# 1_-POWER.net
KiCad netlist of a schematic drawn in Altium Designer
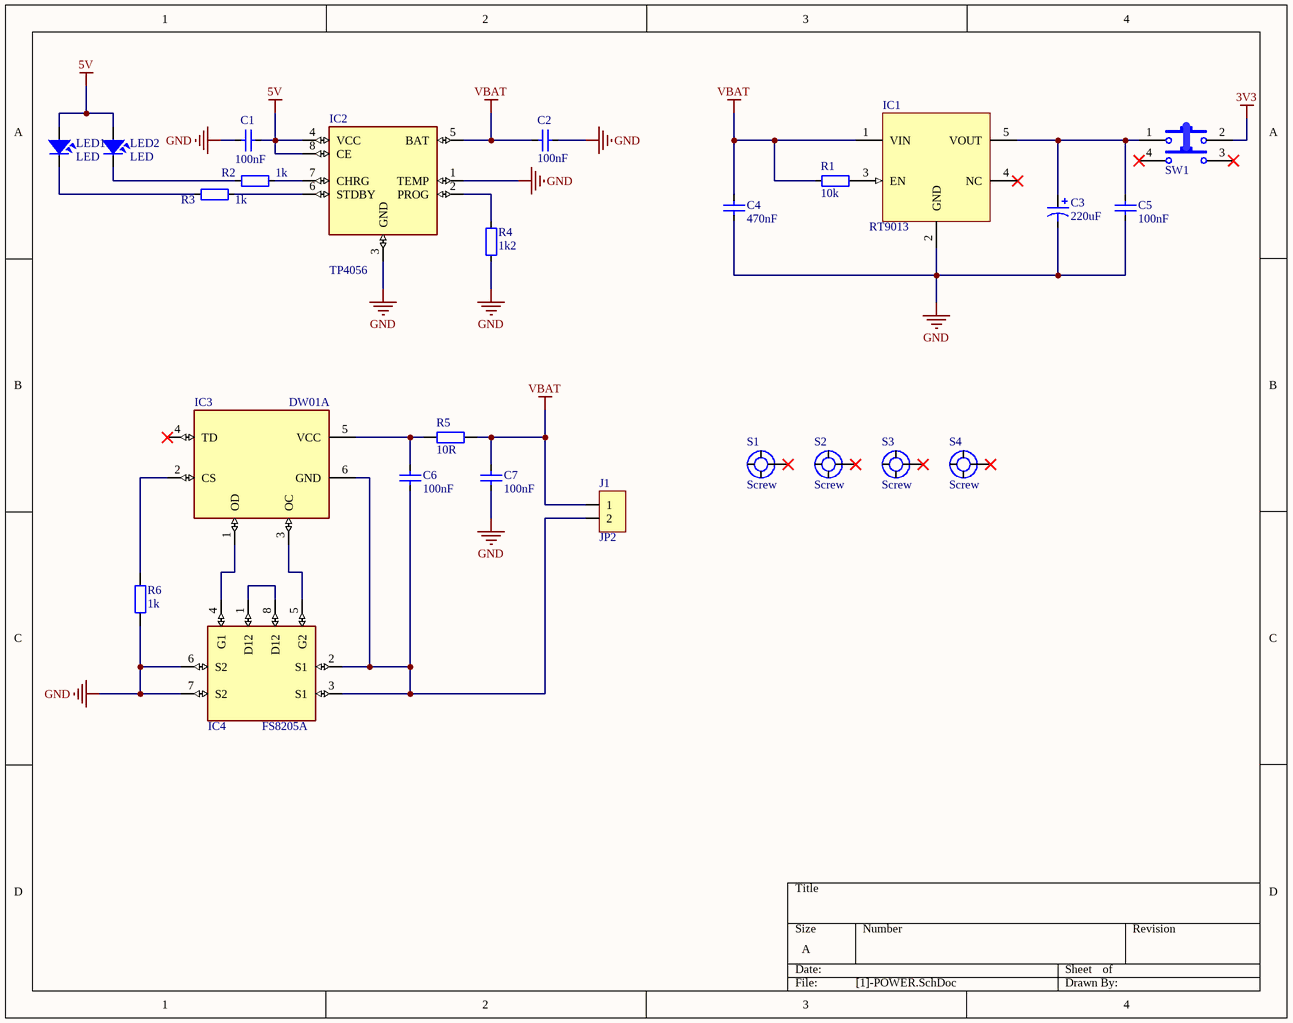
[diagram p0: [1]-POWER.SchDoc]

(export (version "E")
  (design (tool "Eeschema 10.0.6"))
  (components
    (comp (ref "C1")
      (value "100nF")
      (footprint "CAP_0805")
      (description "Capacitor")
      (fields (field (name "PUBLISHER") "Altium Limited"))
      (libsource (lib "My Library") (part "CapSMD"))
    )
    (comp (ref "C2")
      (value "100nF")
      (footprint "CAP_0805")
      (description "Capacitor")
      (fields (field (name "PUBLISHER") "Altium Limited"))
      (libsource (lib "My Library") (part "CapSMD"))
    )
    (comp (ref "C3")
      (value "220uF")
      (footprint "CAP_TANTALUM_3216")
      (description "Polarized Capacitor (Axial)")
      (fields (field (name "PUBLISHER") "Altium Limited"))
      (libsource (lib "My Library") (part "Cap Pol"))
    )
    (comp (ref "C4")
      (value "470nF")
      (footprint "CAP_0805")
      (description "Capacitor")
      (fields (field (name "PUBLISHER") "Altium Limited"))
      (libsource (lib "My Library") (part "CapSMD"))
    )
    (comp (ref "C5")
      (value "100nF")
      (footprint "CAP_0805")
      (description "Capacitor")
      (fields (field (name "PUBLISHER") "Altium Limited"))
      (libsource (lib "My Library") (part "CapSMD"))
    )
    (comp (ref "C6")
      (value "100nF")
      (footprint "CAP_0805")
      (description "Capacitor")
      (fields (field (name "PUBLISHER") "Altium Limited"))
      (libsource (lib "My Library") (part "CapSMD"))
    )
    (comp (ref "C7")
      (value "100nF")
      (footprint "CAP_0805")
      (description "Capacitor")
      (fields (field (name "PUBLISHER") "Altium Limited"))
      (libsource (lib "My Library") (part "CapSMD"))
    )
    (comp (ref "IC1")
      (value "RT9013")
      (footprint "SOT23-5")
      (description "RT9013-33GB IC REG LINEAR 3.3V 500mA SOT23-5")
      (libsource (lib "My Library") (part "RT9013"))
    )
    (comp (ref "IC2")
      (value "TP4056")
      (footprint "SOP127P600X175-9N")
      (description "Complete single cell Li-Ion battery with a constant current / constant voltage linear charger")
      (libsource (lib "My Library") (part "TP4056"))
    )
    (comp (ref "IC3")
      (value "DW01A")
      (footprint "SOT23-6")
      (description "One Cell Lithium-ion/Polymer Battery Protection IC")
      (libsource (lib "My Library") (part "DW01A"))
    )
    (comp (ref "IC4") (value "FS8205A") (footprint "FS8205A") (libsource (lib "My Library") (part "FS8205A")))
    (comp (ref "J1")
      (value "JP2")
      (footprint "CON2")
      (description "WR-PHD 2.54 mm Angled Socket Header")
      (fields
        (field (name "MANUFACTURER") "Würth Elektronik eiSos GmbH")
        (field (name "PARTNO") "613002143121")
        (field (name "CREATED BY") "Karrer Zheng")
      )
      (libsource (lib "My Library") (part "JP2"))
    )
    (comp (ref "LED1")
      (value "LED")
      (footprint "LED-0805-Red")
      (description "LED Single colour Green and Red")
      (libsource (lib "My Library") (part "LED"))
    )
    (comp (ref "LED2")
      (value "LED")
      (footprint "LED-0805-Green")
      (description "LED Single colour Green and Red")
      (libsource (lib "My Library") (part "LED"))
    )
    (comp (ref "R1")
      (value "10k")
      (footprint "RES-SMD-0805")
      (description "Resistor")
      (fields
        (field (name "MANUFACTURER") "Generic Components")
        (field (name "PUBLISHER") "Altium Hobart Technology Centre")
      )
      (libsource (lib "My Library") (part "Resistor - SMD"))
    )
    (comp (ref "R2")
      (value "1k")
      (footprint "RES-SMD-0805")
      (description "Resistor")
      (fields
        (field (name "MANUFACTURER") "Generic Components")
        (field (name "PUBLISHER") "Altium Hobart Technology Centre")
      )
      (libsource (lib "My Library") (part "Resistor - SMD"))
    )
    (comp (ref "R3")
      (value "1k")
      (footprint "RES-SMD-0805")
      (description "Resistor")
      (fields
        (field (name "MANUFACTURER") "Generic Components")
        (field (name "PUBLISHER") "Altium Hobart Technology Centre")
      )
      (libsource (lib "My Library") (part "Resistor - SMD"))
    )
    (comp (ref "R4")
      (value "1k2")
      (footprint "RES-SMD-0805")
      (description "Resistor")
      (fields
        (field (name "MANUFACTURER") "Generic Components")
        (field (name "PUBLISHER") "Altium Hobart Technology Centre")
      )
      (libsource (lib "My Library") (part "Resistor - SMD"))
    )
    (comp (ref "R5")
      (value "10R")
      (footprint "RES-SMD-0805")
      (description "Resistor SMD")
      (fields
        (field (name "MANUFACTURER") "Generic Components")
        (field (name "PUBLISHER") "Altium Hobart Technology Centre")
      )
      (libsource (lib "") (part "Resistor - SMD_1"))
    )
    (comp (ref "R6")
      (value "1k")
      (footprint "RES-SMD-0805")
      (description "Resistor SMD")
      (fields
        (field (name "MANUFACTURER") "Generic Components")
        (field (name "PUBLISHER") "Altium Hobart Technology Centre")
      )
      (libsource (lib "") (part "Resistor - SMD_1"))
    )
    (comp (ref "S1")
      (value "Screw")
      (footprint "LPON_OTHER:Screw 3 small")
      (libsource (lib "lpson") (part "Screw"))
    )
    (comp (ref "S2")
      (value "Screw")
      (footprint "LPON_OTHER:Screw 3 small")
      (libsource (lib "lpson") (part "Screw"))
    )
    (comp (ref "S3")
      (value "Screw")
      (footprint "LPON_OTHER:Screw 3 small")
      (libsource (lib "lpson") (part "Screw"))
    )
    (comp (ref "S4")
      (value "Screw")
      (footprint "LPON_OTHER:Screw 3 small")
      (libsource (lib "lpson") (part "Screw"))
    )
    (comp (ref "SW1")
      (value "SW-4P-B")
      (footprint "SW-4P-B")
      (description "Switch Big 4 Pin")
      (fields (field (name "PUBLISHER") "Altium Limited"))
      (libsource (lib "My Library") (part "SW-4PIN-BIG"))
    )
  )
  (nets
    (net (code "1") (name "3V3") (class "Default")
      (node (ref "SW1") (pin "2") (pinfunction "2_2") (pintype "passive"))
    )
    (net (code "2") (name "5V") (class "Default")
      (node (ref "C1") (pin "1") (pinfunction "1_1") (pintype "passive"))
      (node (ref "IC2") (pin "4") (pinfunction "VCC_4") (pintype "bidirectional"))
      (node (ref "IC2") (pin "8") (pinfunction "CE_8") (pintype "bidirectional"))
      (node (ref "LED1") (pin "1") (pinfunction "1_1") (pintype "passive"))
      (node (ref "LED2") (pin "1") (pinfunction "1_1") (pintype "passive"))
    )
    (net (code "3") (name "GND") (class "Default")
      (node (ref "C1") (pin "2") (pinfunction "2_2") (pintype "passive"))
      (node (ref "C2") (pin "1") (pinfunction "1_1") (pintype "passive"))
      (node (ref "C3") (pin "2") (pinfunction "2_2") (pintype "passive"))
      (node (ref "C4") (pin "2") (pinfunction "2_2") (pintype "passive"))
      (node (ref "C5") (pin "2") (pinfunction "2_2") (pintype "passive"))
      (node (ref "C7") (pin "1") (pinfunction "1_1") (pintype "passive"))
      (node (ref "IC1") (pin "2") (pinfunction "GND_2") (pintype "power_in"))
      (node (ref "IC2") (pin "1") (pinfunction "TEMP_1") (pintype "bidirectional"))
      (node (ref "IC2") (pin "3") (pinfunction "GND_3") (pintype "bidirectional"))
      (node (ref "IC4") (pin "6") (pinfunction "S2_6") (pintype "bidirectional"))
      (node (ref "IC4") (pin "7") (pinfunction "S2_7") (pintype "bidirectional"))
      (node (ref "R4") (pin "1") (pinfunction "1_1") (pintype "passive"))
      (node (ref "R6") (pin "2") (pinfunction "2_2") (pintype "passive"))
    )
    (net (code "4") (name "Net-(IC1-EN)") (class "Default")
      (node (ref "IC1") (pin "3") (pinfunction "EN_3") (pintype "input"))
      (node (ref "R1") (pin "1") (pinfunction "1_1") (pintype "passive"))
    )
    (net (code "5") (name "Net-(IC1-VOUT)") (class "Default")
      (node (ref "C3") (pin "1") (pinfunction "1_1") (pintype "passive"))
      (node (ref "C5") (pin "1") (pinfunction "1_1") (pintype "passive"))
      (node (ref "IC1") (pin "5") (pinfunction "VOUT_5") (pintype "power_in"))
      (node (ref "SW1") (pin "1") (pinfunction "1_1") (pintype "passive"))
    )
    (net (code "6") (name "Net-(IC2-CHRG)") (class "Default")
      (node (ref "IC2") (pin "7") (pinfunction "CHRG_7") (pintype "bidirectional"))
      (node (ref "R2") (pin "1") (pinfunction "1_1") (pintype "passive"))
    )
    (net (code "7") (name "Net-(IC2-PROG)") (class "Default")
      (node (ref "IC2") (pin "2") (pinfunction "PROG_2") (pintype "bidirectional"))
      (node (ref "R4") (pin "2") (pinfunction "2_2") (pintype "passive"))
    )
    (net (code "8") (name "Net-(IC2-STDBY)") (class "Default")
      (node (ref "IC2") (pin "6") (pinfunction "STDBY_6") (pintype "bidirectional"))
      (node (ref "R3") (pin "1") (pinfunction "1_1") (pintype "passive"))
    )
    (net (code "9") (name "Net-(IC3-CS)") (class "Default")
      (node (ref "IC3") (pin "2") (pinfunction "CS_2") (pintype "bidirectional"))
      (node (ref "R6") (pin "1") (pinfunction "1_1") (pintype "passive"))
    )
    (net (code "10") (name "Net-(IC3-GND)") (class "Default")
      (node (ref "C6") (pin "1") (pinfunction "1_1") (pintype "passive"))
      (node (ref "IC3") (pin "6") (pinfunction "GND_6") (pintype "power_in"))
      (node (ref "IC4") (pin "2") (pinfunction "S1_2") (pintype "bidirectional"))
      (node (ref "IC4") (pin "3") (pinfunction "S1_3") (pintype "bidirectional"))
      (node (ref "J1") (pin "2") (pinfunction "2_2") (pintype "passive"))
    )
    (net (code "11") (name "Net-(IC3-OC)") (class "Default")
      (node (ref "IC3") (pin "3") (pinfunction "OC_3") (pintype "bidirectional"))
      (node (ref "IC4") (pin "5") (pinfunction "G2_5") (pintype "bidirectional"))
    )
    (net (code "12") (name "Net-(IC3-OD)") (class "Default")
      (node (ref "IC3") (pin "1") (pinfunction "OD_1") (pintype "bidirectional"))
      (node (ref "IC4") (pin "4") (pinfunction "G1_4") (pintype "bidirectional"))
    )
    (net (code "13") (name "Net-(IC3-VCC)") (class "Default")
      (node (ref "C6") (pin "2") (pinfunction "2_2") (pintype "passive"))
      (node (ref "IC3") (pin "5") (pinfunction "VCC_5") (pintype "power_in"))
      (node (ref "R5") (pin "1") (pinfunction "1_1") (pintype "passive"))
    )
    (net (code "14") (name "Net-(IC4-D12-Pad1)") (class "Default")
      (node (ref "IC4") (pin "1") (pinfunction "D12_1") (pintype "bidirectional"))
      (node (ref "IC4") (pin "8") (pinfunction "D12_8") (pintype "bidirectional"))
    )
    (net (code "15") (name "Net-(LED1-Pad2)") (class "Default")
      (node (ref "LED1") (pin "2") (pinfunction "2_2") (pintype "passive"))
      (node (ref "R3") (pin "2") (pinfunction "2_2") (pintype "passive"))
    )
    (net (code "16") (name "Net-(LED2-Pad2)") (class "Default")
      (node (ref "LED2") (pin "2") (pinfunction "2_2") (pintype "passive"))
      (node (ref "R2") (pin "2") (pinfunction "2_2") (pintype "passive"))
    )
    (net (code "17") (name "VBAT") (class "Default")
      (node (ref "C2") (pin "2") (pinfunction "2_2") (pintype "passive"))
      (node (ref "C4") (pin "1") (pinfunction "1_1") (pintype "passive"))
      (node (ref "C7") (pin "2") (pinfunction "2_2") (pintype "passive"))
      (node (ref "IC1") (pin "1") (pinfunction "VIN_1") (pintype "power_in"))
      (node (ref "IC2") (pin "5") (pinfunction "BAT_5") (pintype "bidirectional"))
      (node (ref "J1") (pin "1") (pinfunction "1_1") (pintype "passive"))
      (node (ref "R1") (pin "2") (pinfunction "2_2") (pintype "passive"))
      (node (ref "R5") (pin "2") (pinfunction "2_2") (pintype "passive"))
    )
    (net (code "18") (name "unconnected-(IC1-NC-Pad4)") (class "Default")
      (node (ref "IC1") (pin "4") (pinfunction "NC_4") (pintype "passive+no_connect"))
    )
    (net (code "19") (name "unconnected-(IC3-TD-Pad4)") (class "Default")
      (node (ref "IC3") (pin "4") (pinfunction "TD_4") (pintype "bidirectional+no_connect"))
    )
    (net (code "20") (name "unconnected-(S1-Pad1)") (class "Default")
      (node (ref "S1") (pin "1") (pinfunction "1_1") (pintype "passive+no_connect"))
    )
    (net (code "21") (name "unconnected-(S2-Pad1)") (class "Default")
      (node (ref "S2") (pin "1") (pinfunction "1_1") (pintype "passive+no_connect"))
    )
    (net (code "22") (name "unconnected-(S3-Pad1)") (class "Default")
      (node (ref "S3") (pin "1") (pinfunction "1_1") (pintype "passive+no_connect"))
    )
    (net (code "23") (name "unconnected-(S4-Pad1)") (class "Default")
      (node (ref "S4") (pin "1") (pinfunction "1_1") (pintype "passive+no_connect"))
    )
    (net (code "24") (name "unconnected-(SW1-Pad3)") (class "Default")
      (node (ref "SW1") (pin "3") (pinfunction "3_3") (pintype "passive+no_connect"))
    )
    (net (code "25") (name "unconnected-(SW1-Pad4)") (class "Default")
      (node (ref "SW1") (pin "4") (pinfunction "4_4") (pintype "passive+no_connect"))
    )
  )
)
